# 6_Channel_Pulse_Generator.net
KiCad netlist of a schematic drawn in EAGLE
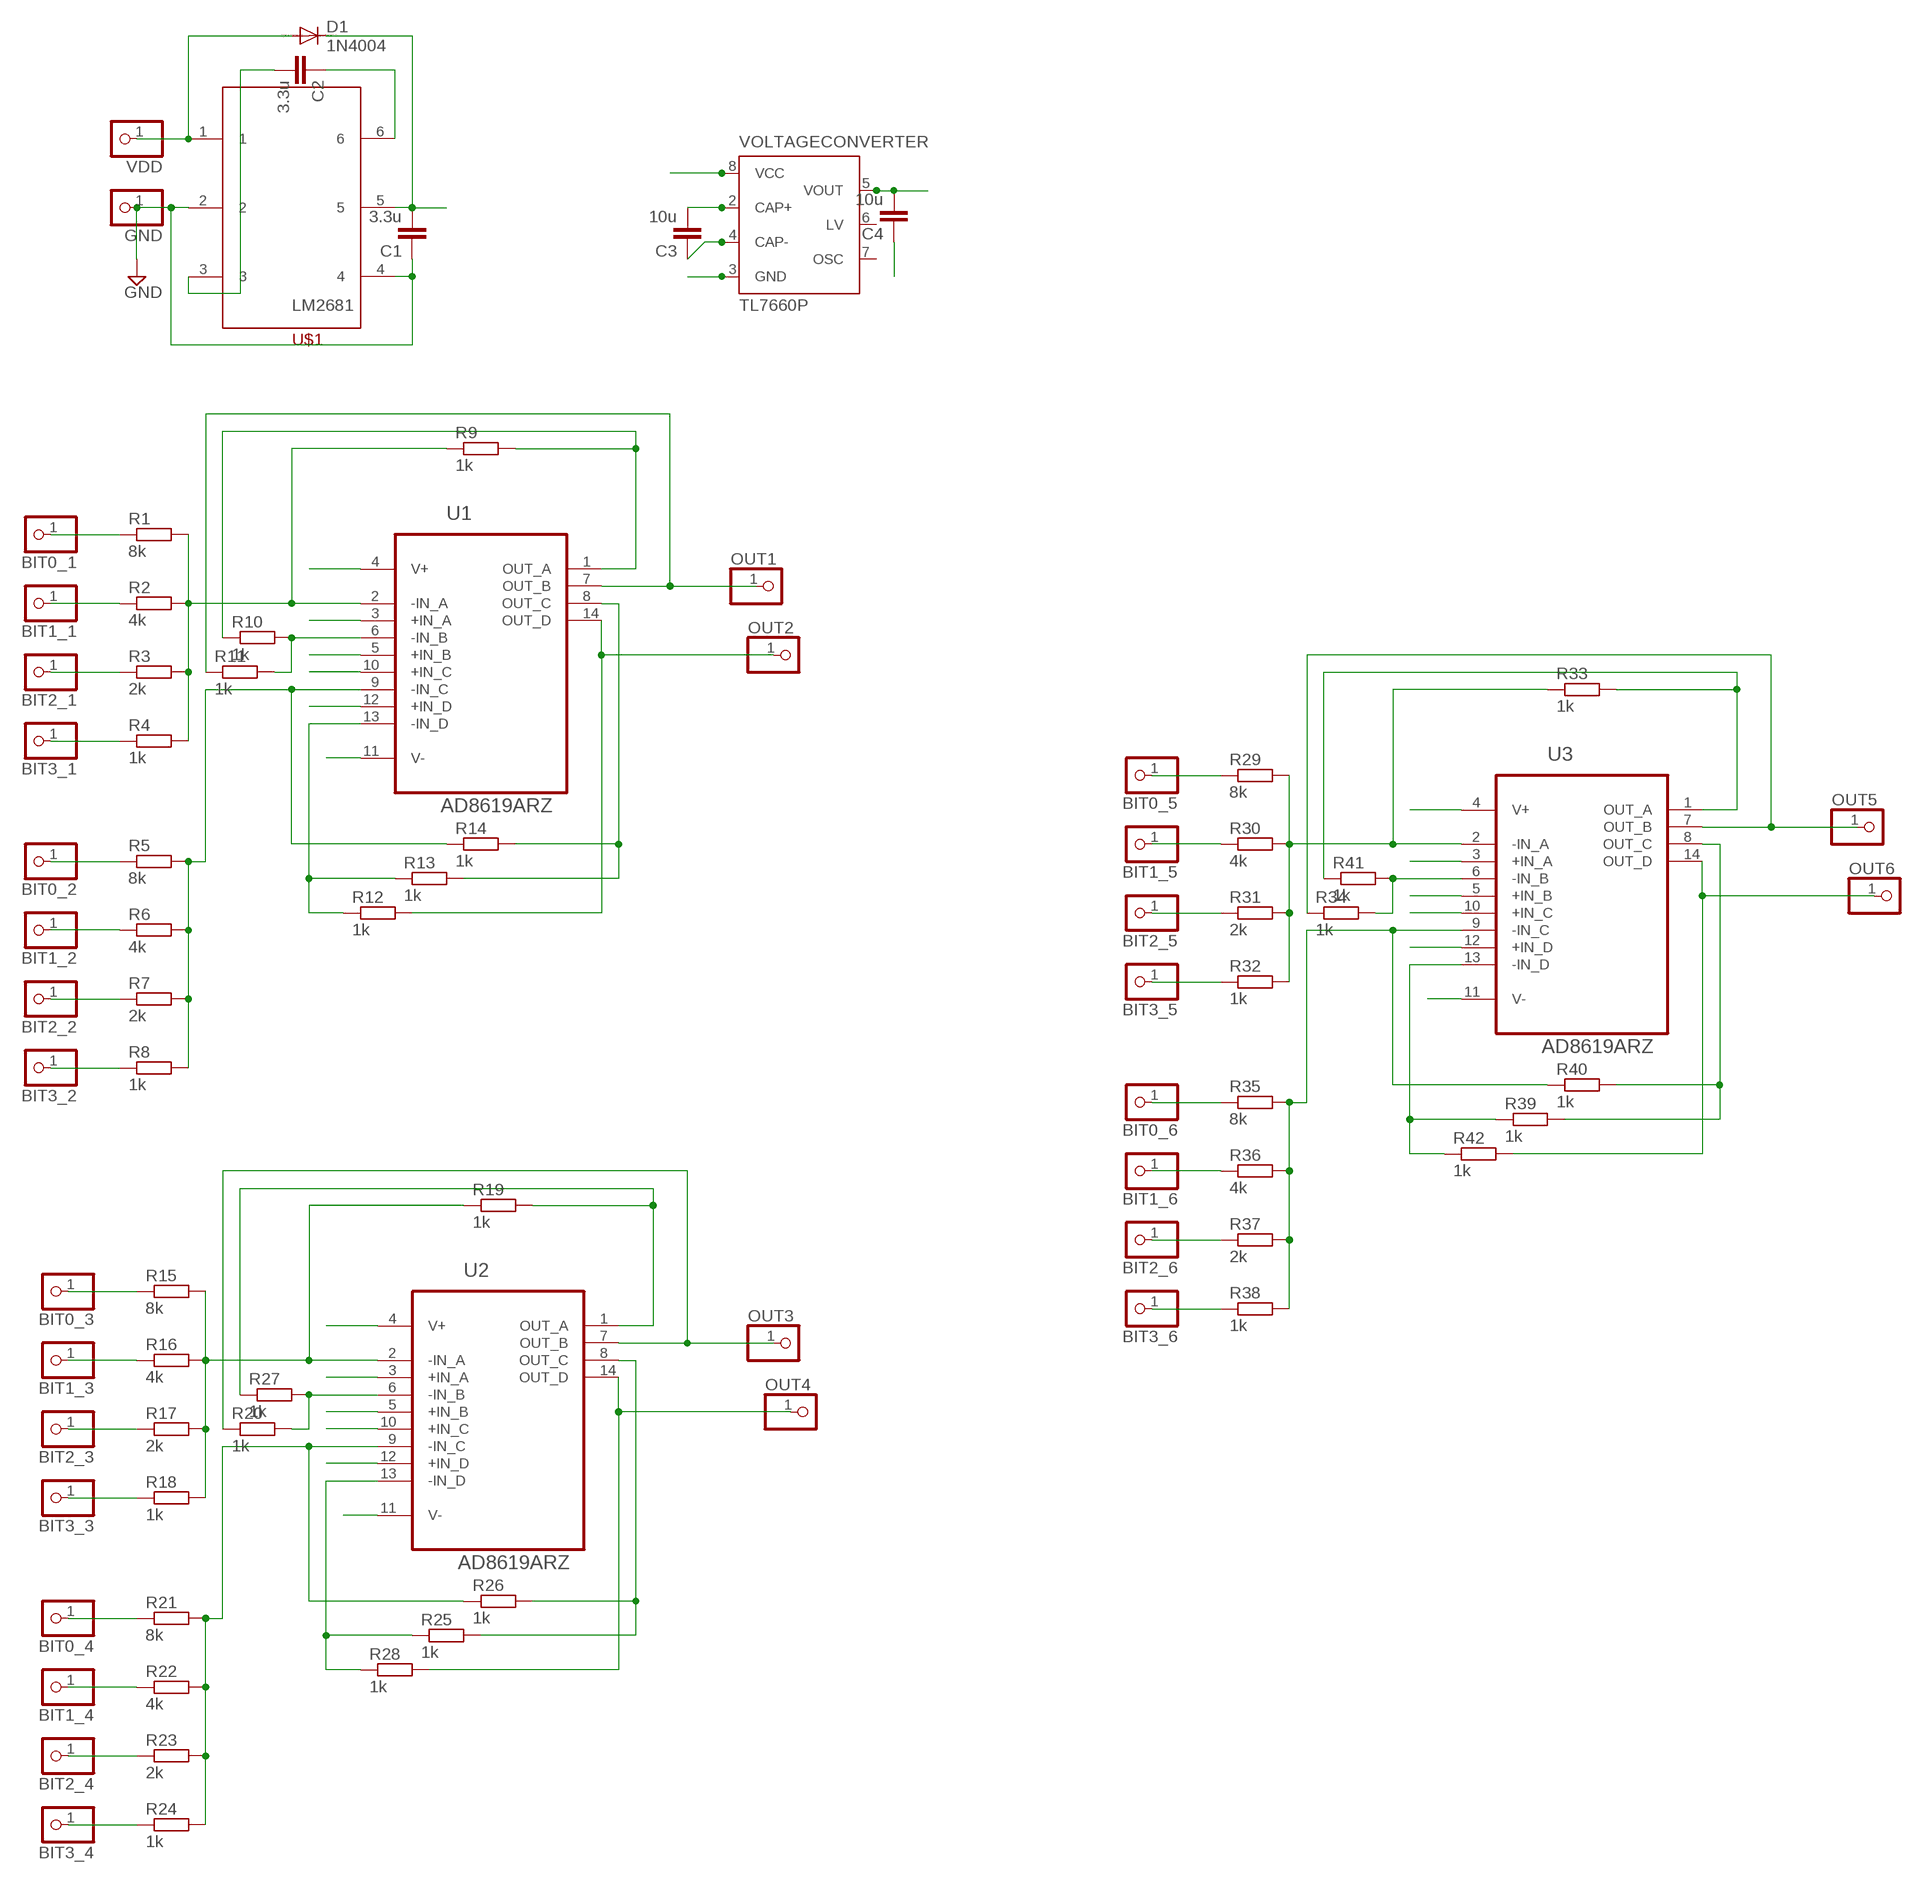
[diagram p0: schematic, sheet 1]

(export (version "E")
  (design (tool "Eeschema 10.0.6"))
  (components
    (comp (ref "BIT0_1")
      (value "PINHD-1X1")
      (footprint "eagle-import:1X01")
      (libsource (lib "eagle-import") (part "PINHD-1X1"))
    )
    (comp (ref "BIT0_2")
      (value "PINHD-1X1")
      (footprint "eagle-import:1X01")
      (libsource (lib "eagle-import") (part "PINHD-1X1"))
    )
    (comp (ref "BIT0_3")
      (value "PINHD-1X1")
      (footprint "eagle-import:1X01")
      (libsource (lib "eagle-import") (part "PINHD-1X1"))
    )
    (comp (ref "BIT0_4")
      (value "PINHD-1X1")
      (footprint "eagle-import:1X01")
      (libsource (lib "eagle-import") (part "PINHD-1X1"))
    )
    (comp (ref "BIT0_5")
      (value "PINHD-1X1")
      (footprint "eagle-import:1X01")
      (libsource (lib "eagle-import") (part "PINHD-1X1"))
    )
    (comp (ref "BIT0_6")
      (value "PINHD-1X1")
      (footprint "eagle-import:1X01")
      (libsource (lib "eagle-import") (part "PINHD-1X1"))
    )
    (comp (ref "BIT1_1")
      (value "PINHD-1X1")
      (footprint "eagle-import:1X01")
      (libsource (lib "eagle-import") (part "PINHD-1X1"))
    )
    (comp (ref "BIT1_2")
      (value "PINHD-1X1")
      (footprint "eagle-import:1X01")
      (libsource (lib "eagle-import") (part "PINHD-1X1"))
    )
    (comp (ref "BIT1_3")
      (value "PINHD-1X1")
      (footprint "eagle-import:1X01")
      (libsource (lib "eagle-import") (part "PINHD-1X1"))
    )
    (comp (ref "BIT1_4")
      (value "PINHD-1X1")
      (footprint "eagle-import:1X01")
      (libsource (lib "eagle-import") (part "PINHD-1X1"))
    )
    (comp (ref "BIT1_5")
      (value "PINHD-1X1")
      (footprint "eagle-import:1X01")
      (libsource (lib "eagle-import") (part "PINHD-1X1"))
    )
    (comp (ref "BIT1_6")
      (value "PINHD-1X1")
      (footprint "eagle-import:1X01")
      (libsource (lib "eagle-import") (part "PINHD-1X1"))
    )
    (comp (ref "BIT2_1")
      (value "PINHD-1X1")
      (footprint "eagle-import:1X01")
      (libsource (lib "eagle-import") (part "PINHD-1X1"))
    )
    (comp (ref "BIT2_2")
      (value "PINHD-1X1")
      (footprint "eagle-import:1X01")
      (libsource (lib "eagle-import") (part "PINHD-1X1"))
    )
    (comp (ref "BIT2_3")
      (value "PINHD-1X1")
      (footprint "eagle-import:1X01")
      (libsource (lib "eagle-import") (part "PINHD-1X1"))
    )
    (comp (ref "BIT2_4")
      (value "PINHD-1X1")
      (footprint "eagle-import:1X01")
      (libsource (lib "eagle-import") (part "PINHD-1X1"))
    )
    (comp (ref "BIT2_5")
      (value "PINHD-1X1")
      (footprint "eagle-import:1X01")
      (libsource (lib "eagle-import") (part "PINHD-1X1"))
    )
    (comp (ref "BIT2_6")
      (value "PINHD-1X1")
      (footprint "eagle-import:1X01")
      (libsource (lib "eagle-import") (part "PINHD-1X1"))
    )
    (comp (ref "BIT3_1")
      (value "PINHD-1X1")
      (footprint "eagle-import:1X01")
      (libsource (lib "eagle-import") (part "PINHD-1X1"))
    )
    (comp (ref "BIT3_2")
      (value "PINHD-1X1")
      (footprint "eagle-import:1X01")
      (libsource (lib "eagle-import") (part "PINHD-1X1"))
    )
    (comp (ref "BIT3_3")
      (value "PINHD-1X1")
      (footprint "eagle-import:1X01")
      (libsource (lib "eagle-import") (part "PINHD-1X1"))
    )
    (comp (ref "BIT3_4")
      (value "PINHD-1X1")
      (footprint "eagle-import:1X01")
      (libsource (lib "eagle-import") (part "PINHD-1X1"))
    )
    (comp (ref "BIT3_5")
      (value "PINHD-1X1")
      (footprint "eagle-import:1X01")
      (libsource (lib "eagle-import") (part "PINHD-1X1"))
    )
    (comp (ref "BIT3_6")
      (value "PINHD-1X1")
      (footprint "eagle-import:1X01")
      (libsource (lib "eagle-import") (part "PINHD-1X1"))
    )
    (comp (ref "C1")
      (value "3.3u")
      (footprint "eagle-import:C1206")
      (libsource (lib "eagle-import") (part "C-EUC1206"))
    )
    (comp (ref "C2")
      (value "3.3u")
      (footprint "eagle-import:C1206")
      (libsource (lib "eagle-import") (part "C-EUC1206"))
    )
    (comp (ref "C3")
      (value "10u")
      (footprint "eagle-import:C1206")
      (libsource (lib "eagle-import") (part "C-EUC1206"))
    )
    (comp (ref "C4")
      (value "10u")
      (footprint "eagle-import:C1206")
      (libsource (lib "eagle-import") (part "C-EUC1206"))
    )
    (comp (ref "D1")
      (value "1N4004")
      (footprint "eagle-import:DO41-10")
      (libsource (lib "eagle-import") (part "1N4004"))
    )
    (comp (ref "GND")
      (value "PINHD-1X1")
      (footprint "eagle-import:1X01")
      (libsource (lib "eagle-import") (part "PINHD-1X1"))
    )
    (comp (ref "OUT1")
      (value "PINHD-1X1")
      (footprint "eagle-import:1X01")
      (libsource (lib "eagle-import") (part "PINHD-1X1"))
    )
    (comp (ref "OUT2")
      (value "PINHD-1X1")
      (footprint "eagle-import:1X01")
      (libsource (lib "eagle-import") (part "PINHD-1X1"))
    )
    (comp (ref "OUT3")
      (value "PINHD-1X1")
      (footprint "eagle-import:1X01")
      (libsource (lib "eagle-import") (part "PINHD-1X1"))
    )
    (comp (ref "OUT4")
      (value "PINHD-1X1")
      (footprint "eagle-import:1X01")
      (libsource (lib "eagle-import") (part "PINHD-1X1"))
    )
    (comp (ref "OUT5")
      (value "PINHD-1X1")
      (footprint "eagle-import:1X01")
      (libsource (lib "eagle-import") (part "PINHD-1X1"))
    )
    (comp (ref "OUT6")
      (value "PINHD-1X1")
      (footprint "eagle-import:1X01")
      (libsource (lib "eagle-import") (part "PINHD-1X1"))
    )
    (comp (ref "R1")
      (value "8k")
      (footprint "eagle-import:M1206")
      (libsource (lib "eagle-import") (part "R-EU_M1206"))
    )
    (comp (ref "R2")
      (value "4k")
      (footprint "eagle-import:M1206")
      (libsource (lib "eagle-import") (part "R-EU_M1206"))
    )
    (comp (ref "R3")
      (value "2k")
      (footprint "eagle-import:M1206")
      (libsource (lib "eagle-import") (part "R-EU_M1206"))
    )
    (comp (ref "R4")
      (value "1k")
      (footprint "eagle-import:M1206")
      (libsource (lib "eagle-import") (part "R-EU_M1206"))
    )
    (comp (ref "R5")
      (value "8k")
      (footprint "eagle-import:M1206")
      (libsource (lib "eagle-import") (part "R-EU_M1206"))
    )
    (comp (ref "R6")
      (value "4k")
      (footprint "eagle-import:M1206")
      (libsource (lib "eagle-import") (part "R-EU_M1206"))
    )
    (comp (ref "R7")
      (value "2k")
      (footprint "eagle-import:M1206")
      (libsource (lib "eagle-import") (part "R-EU_M1206"))
    )
    (comp (ref "R8")
      (value "1k")
      (footprint "eagle-import:M1206")
      (libsource (lib "eagle-import") (part "R-EU_M1206"))
    )
    (comp (ref "R9")
      (value "1k")
      (footprint "eagle-import:M1206")
      (libsource (lib "eagle-import") (part "R-EU_M1206"))
    )
    (comp (ref "R10")
      (value "1k")
      (footprint "eagle-import:M1206")
      (libsource (lib "eagle-import") (part "R-EU_M1206"))
    )
    (comp (ref "R11")
      (value "1k")
      (footprint "eagle-import:M1206")
      (libsource (lib "eagle-import") (part "R-EU_M1206"))
    )
    (comp (ref "R12")
      (value "1k")
      (footprint "eagle-import:M1206")
      (libsource (lib "eagle-import") (part "R-EU_M1206"))
    )
    (comp (ref "R13")
      (value "1k")
      (footprint "eagle-import:M1206")
      (libsource (lib "eagle-import") (part "R-EU_M1206"))
    )
    (comp (ref "R14")
      (value "1k")
      (footprint "eagle-import:M1206")
      (libsource (lib "eagle-import") (part "R-EU_M1206"))
    )
    (comp (ref "R15")
      (value "8k")
      (footprint "eagle-import:M1206")
      (libsource (lib "eagle-import") (part "R-EU_M1206"))
    )
    (comp (ref "R16")
      (value "4k")
      (footprint "eagle-import:M1206")
      (libsource (lib "eagle-import") (part "R-EU_M1206"))
    )
    (comp (ref "R17")
      (value "2k")
      (footprint "eagle-import:M1206")
      (libsource (lib "eagle-import") (part "R-EU_M1206"))
    )
    (comp (ref "R18")
      (value "1k")
      (footprint "eagle-import:M1206")
      (libsource (lib "eagle-import") (part "R-EU_M1206"))
    )
    (comp (ref "R19")
      (value "1k")
      (footprint "eagle-import:M1206")
      (libsource (lib "eagle-import") (part "R-EU_M1206"))
    )
    (comp (ref "R20")
      (value "1k")
      (footprint "eagle-import:M1206")
      (libsource (lib "eagle-import") (part "R-EU_M1206"))
    )
    (comp (ref "R21")
      (value "8k")
      (footprint "eagle-import:M1206")
      (libsource (lib "eagle-import") (part "R-EU_M1206"))
    )
    (comp (ref "R22")
      (value "4k")
      (footprint "eagle-import:M1206")
      (libsource (lib "eagle-import") (part "R-EU_M1206"))
    )
    (comp (ref "R23")
      (value "2k")
      (footprint "eagle-import:M1206")
      (libsource (lib "eagle-import") (part "R-EU_M1206"))
    )
    (comp (ref "R24")
      (value "1k")
      (footprint "eagle-import:M1206")
      (libsource (lib "eagle-import") (part "R-EU_M1206"))
    )
    (comp (ref "R25")
      (value "1k")
      (footprint "eagle-import:M1206")
      (libsource (lib "eagle-import") (part "R-EU_M1206"))
    )
    (comp (ref "R26")
      (value "1k")
      (footprint "eagle-import:M1206")
      (libsource (lib "eagle-import") (part "R-EU_M1206"))
    )
    (comp (ref "R27")
      (value "1k")
      (footprint "eagle-import:M1206")
      (libsource (lib "eagle-import") (part "R-EU_M1206"))
    )
    (comp (ref "R28")
      (value "1k")
      (footprint "eagle-import:M1206")
      (libsource (lib "eagle-import") (part "R-EU_M1206"))
    )
    (comp (ref "R29")
      (value "8k")
      (footprint "eagle-import:M1206")
      (libsource (lib "eagle-import") (part "R-EU_M1206"))
    )
    (comp (ref "R30")
      (value "4k")
      (footprint "eagle-import:M1206")
      (libsource (lib "eagle-import") (part "R-EU_M1206"))
    )
    (comp (ref "R31")
      (value "2k")
      (footprint "eagle-import:M1206")
      (libsource (lib "eagle-import") (part "R-EU_M1206"))
    )
    (comp (ref "R32")
      (value "1k")
      (footprint "eagle-import:M1206")
      (libsource (lib "eagle-import") (part "R-EU_M1206"))
    )
    (comp (ref "R33")
      (value "1k")
      (footprint "eagle-import:M1206")
      (libsource (lib "eagle-import") (part "R-EU_M1206"))
    )
    (comp (ref "R34")
      (value "1k")
      (footprint "eagle-import:M1206")
      (libsource (lib "eagle-import") (part "R-EU_M1206"))
    )
    (comp (ref "R35")
      (value "8k")
      (footprint "eagle-import:M1206")
      (libsource (lib "eagle-import") (part "R-EU_M1206"))
    )
    (comp (ref "R36")
      (value "4k")
      (footprint "eagle-import:M1206")
      (libsource (lib "eagle-import") (part "R-EU_M1206"))
    )
    (comp (ref "R37")
      (value "2k")
      (footprint "eagle-import:M1206")
      (libsource (lib "eagle-import") (part "R-EU_M1206"))
    )
    (comp (ref "R38")
      (value "1k")
      (footprint "eagle-import:M1206")
      (libsource (lib "eagle-import") (part "R-EU_M1206"))
    )
    (comp (ref "R39")
      (value "1k")
      (footprint "eagle-import:M1206")
      (libsource (lib "eagle-import") (part "R-EU_M1206"))
    )
    (comp (ref "R40")
      (value "1k")
      (footprint "eagle-import:M1206")
      (libsource (lib "eagle-import") (part "R-EU_M1206"))
    )
    (comp (ref "R41")
      (value "1k")
      (footprint "eagle-import:M1206")
      (libsource (lib "eagle-import") (part "R-EU_M1206"))
    )
    (comp (ref "R42")
      (value "1k")
      (footprint "eagle-import:M1206")
      (libsource (lib "eagle-import") (part "R-EU_M1206"))
    )
    (comp (ref "U$1")
      (value "LM2681")
      (footprint "eagle-import:LM2681")
      (libsource (lib "eagle-import") (part "LM2681"))
    )
    (comp (ref "U1")
      (value "AD8619ARZ")
      (footprint "eagle-import:SOIC127P600X175-14N")
      (fields (field (name "MF") "Analog Devices"))
      (libsource (lib "eagle-import") (part "AD8619ARZ"))
    )
    (comp (ref "U2")
      (value "AD8619ARZ")
      (footprint "eagle-import:SOIC127P600X175-14N")
      (fields (field (name "MF") "Analog Devices"))
      (libsource (lib "eagle-import") (part "AD8619ARZ"))
    )
    (comp (ref "U3")
      (value "AD8619ARZ")
      (footprint "eagle-import:SOIC127P600X175-14N")
      (fields (field (name "MF") "Analog Devices"))
      (libsource (lib "eagle-import") (part "AD8619ARZ"))
    )
    (comp (ref "VDD")
      (value "PINHD-1X1")
      (footprint "eagle-import:1X01")
      (libsource (lib "eagle-import") (part "PINHD-1X1"))
    )
    (comp (ref "VOLTAGECONVERTER")
      (value "TL7660P")
      (footprint "eagle-import:DIL08")
      (fields (field (name "MPN") "TL7660CP"))
      (libsource (lib "eagle-import") (part "TL7660P"))
    )
  )
  (nets
    (net (code "1") (name "/VDD") (class "Default")
      (node (ref "C1") (pin "2") (pinfunction "2_2") (pintype "passive"))
      (node (ref "D1") (pin "C") (pinfunction "C_C") (pintype "passive"))
      (node (ref "U$1") (pin "5") (pinfunction "5_5") (pintype "bidirectional"))
      (node (ref "U1") (pin "4") (pinfunction "V+_4") (pintype "power_in"))
      (node (ref "U2") (pin "4") (pinfunction "V+_4") (pintype "power_in"))
      (node (ref "U3") (pin "4") (pinfunction "V+_4") (pintype "power_in"))
      (node (ref "VOLTAGECONVERTER") (pin "8") (pinfunction "VCC_8") (pintype "power_in"))
    )
    (net (code "2") (name "/VDD-") (class "Default")
      (node (ref "C4") (pin "2") (pinfunction "2_2") (pintype "passive"))
      (node (ref "U1") (pin "11") (pinfunction "V-_11") (pintype "power_in"))
      (node (ref "U2") (pin "11") (pinfunction "V-_11") (pintype "power_in"))
      (node (ref "U3") (pin "11") (pinfunction "V-_11") (pintype "power_in"))
      (node (ref "VOLTAGECONVERTER") (pin "5") (pinfunction "VOUT_5") (pintype "passive"))
    )
    (net (code "3") (name "GND") (class "Default")
      (node (ref "C1") (pin "1") (pinfunction "1_1") (pintype "passive"))
      (node (ref "C4") (pin "1") (pinfunction "1_1") (pintype "passive"))
      (node (ref "GND") (pin "1") (pinfunction "1_1") (pintype "passive"))
      (node (ref "U$1") (pin "2") (pinfunction "2_2") (pintype "bidirectional"))
      (node (ref "U$1") (pin "4") (pinfunction "4_4") (pintype "bidirectional"))
      (node (ref "U1") (pin "10") (pinfunction "+IN_C_10") (pintype "input"))
      (node (ref "U1") (pin "12") (pinfunction "+IN_D_12") (pintype "input"))
      (node (ref "U1") (pin "3") (pinfunction "+IN_A_3") (pintype "input"))
      (node (ref "U1") (pin "5") (pinfunction "+IN_B_5") (pintype "input"))
      (node (ref "U2") (pin "10") (pinfunction "+IN_C_10") (pintype "input"))
      (node (ref "U2") (pin "12") (pinfunction "+IN_D_12") (pintype "input"))
      (node (ref "U2") (pin "3") (pinfunction "+IN_A_3") (pintype "input"))
      (node (ref "U2") (pin "5") (pinfunction "+IN_B_5") (pintype "input"))
      (node (ref "U3") (pin "10") (pinfunction "+IN_C_10") (pintype "input"))
      (node (ref "U3") (pin "12") (pinfunction "+IN_D_12") (pintype "input"))
      (node (ref "U3") (pin "3") (pinfunction "+IN_A_3") (pintype "input"))
      (node (ref "U3") (pin "5") (pinfunction "+IN_B_5") (pintype "input"))
      (node (ref "VOLTAGECONVERTER") (pin "3") (pinfunction "GND_3") (pintype "power_in"))
    )
    (net (code "4") (name "Net-(BIT0_1-Pad1)") (class "Default")
      (node (ref "BIT0_1") (pin "1") (pinfunction "1_1") (pintype "passive"))
      (node (ref "R1") (pin "1") (pinfunction "1_1") (pintype "passive"))
    )
    (net (code "5") (name "Net-(BIT0_2-Pad1)") (class "Default")
      (node (ref "BIT0_2") (pin "1") (pinfunction "1_1") (pintype "passive"))
      (node (ref "R5") (pin "1") (pinfunction "1_1") (pintype "passive"))
    )
    (net (code "6") (name "Net-(BIT0_3-Pad1)") (class "Default")
      (node (ref "BIT0_3") (pin "1") (pinfunction "1_1") (pintype "passive"))
      (node (ref "R15") (pin "1") (pinfunction "1_1") (pintype "passive"))
    )
    (net (code "7") (name "Net-(BIT0_4-Pad1)") (class "Default")
      (node (ref "BIT0_4") (pin "1") (pinfunction "1_1") (pintype "passive"))
      (node (ref "R21") (pin "1") (pinfunction "1_1") (pintype "passive"))
    )
    (net (code "8") (name "Net-(BIT0_5-Pad1)") (class "Default")
      (node (ref "BIT0_5") (pin "1") (pinfunction "1_1") (pintype "passive"))
      (node (ref "R29") (pin "1") (pinfunction "1_1") (pintype "passive"))
    )
    (net (code "9") (name "Net-(BIT0_6-Pad1)") (class "Default")
      (node (ref "BIT0_6") (pin "1") (pinfunction "1_1") (pintype "passive"))
      (node (ref "R35") (pin "1") (pinfunction "1_1") (pintype "passive"))
    )
    (net (code "10") (name "Net-(BIT1_1-Pad1)") (class "Default")
      (node (ref "BIT1_1") (pin "1") (pinfunction "1_1") (pintype "passive"))
      (node (ref "R2") (pin "1") (pinfunction "1_1") (pintype "passive"))
    )
    (net (code "11") (name "Net-(BIT1_2-Pad1)") (class "Default")
      (node (ref "BIT1_2") (pin "1") (pinfunction "1_1") (pintype "passive"))
      (node (ref "R6") (pin "1") (pinfunction "1_1") (pintype "passive"))
    )
    (net (code "12") (name "Net-(BIT1_3-Pad1)") (class "Default")
      (node (ref "BIT1_3") (pin "1") (pinfunction "1_1") (pintype "passive"))
      (node (ref "R16") (pin "1") (pinfunction "1_1") (pintype "passive"))
    )
    (net (code "13") (name "Net-(BIT1_4-Pad1)") (class "Default")
      (node (ref "BIT1_4") (pin "1") (pinfunction "1_1") (pintype "passive"))
      (node (ref "R22") (pin "1") (pinfunction "1_1") (pintype "passive"))
    )
    (net (code "14") (name "Net-(BIT1_5-Pad1)") (class "Default")
      (node (ref "BIT1_5") (pin "1") (pinfunction "1_1") (pintype "passive"))
      (node (ref "R30") (pin "1") (pinfunction "1_1") (pintype "passive"))
    )
    (net (code "15") (name "Net-(BIT1_6-Pad1)") (class "Default")
      (node (ref "BIT1_6") (pin "1") (pinfunction "1_1") (pintype "passive"))
      (node (ref "R36") (pin "1") (pinfunction "1_1") (pintype "passive"))
    )
    (net (code "16") (name "Net-(BIT2_1-Pad1)") (class "Default")
      (node (ref "BIT2_1") (pin "1") (pinfunction "1_1") (pintype "passive"))
      (node (ref "R3") (pin "1") (pinfunction "1_1") (pintype "passive"))
    )
    (net (code "17") (name "Net-(BIT2_2-Pad1)") (class "Default")
      (node (ref "BIT2_2") (pin "1") (pinfunction "1_1") (pintype "passive"))
      (node (ref "R7") (pin "1") (pinfunction "1_1") (pintype "passive"))
    )
    (net (code "18") (name "Net-(BIT2_3-Pad1)") (class "Default")
      (node (ref "BIT2_3") (pin "1") (pinfunction "1_1") (pintype "passive"))
      (node (ref "R17") (pin "1") (pinfunction "1_1") (pintype "passive"))
    )
    (net (code "19") (name "Net-(BIT2_4-Pad1)") (class "Default")
      (node (ref "BIT2_4") (pin "1") (pinfunction "1_1") (pintype "passive"))
      (node (ref "R23") (pin "1") (pinfunction "1_1") (pintype "passive"))
    )
    (net (code "20") (name "Net-(BIT2_5-Pad1)") (class "Default")
      (node (ref "BIT2_5") (pin "1") (pinfunction "1_1") (pintype "passive"))
      (node (ref "R31") (pin "1") (pinfunction "1_1") (pintype "passive"))
    )
    (net (code "21") (name "Net-(BIT2_6-Pad1)") (class "Default")
      (node (ref "BIT2_6") (pin "1") (pinfunction "1_1") (pintype "passive"))
      (node (ref "R37") (pin "1") (pinfunction "1_1") (pintype "passive"))
    )
    (net (code "22") (name "Net-(BIT3_1-Pad1)") (class "Default")
      (node (ref "BIT3_1") (pin "1") (pinfunction "1_1") (pintype "passive"))
      (node (ref "R4") (pin "1") (pinfunction "1_1") (pintype "passive"))
    )
    (net (code "23") (name "Net-(BIT3_2-Pad1)") (class "Default")
      (node (ref "BIT3_2") (pin "1") (pinfunction "1_1") (pintype "passive"))
      (node (ref "R8") (pin "1") (pinfunction "1_1") (pintype "passive"))
    )
    (net (code "24") (name "Net-(BIT3_3-Pad1)") (class "Default")
      (node (ref "BIT3_3") (pin "1") (pinfunction "1_1") (pintype "passive"))
      (node (ref "R18") (pin "1") (pinfunction "1_1") (pintype "passive"))
    )
    (net (code "25") (name "Net-(BIT3_4-Pad1)") (class "Default")
      (node (ref "BIT3_4") (pin "1") (pinfunction "1_1") (pintype "passive"))
      (node (ref "R24") (pin "1") (pinfunction "1_1") (pintype "passive"))
    )
    (net (code "26") (name "Net-(BIT3_5-Pad1)") (class "Default")
      (node (ref "BIT3_5") (pin "1") (pinfunction "1_1") (pintype "passive"))
      (node (ref "R32") (pin "1") (pinfunction "1_1") (pintype "passive"))
    )
    (net (code "27") (name "Net-(BIT3_6-Pad1)") (class "Default")
      (node (ref "BIT3_6") (pin "1") (pinfunction "1_1") (pintype "passive"))
      (node (ref "R38") (pin "1") (pinfunction "1_1") (pintype "passive"))
    )
    (net (code "28") (name "Net-(C2-Pad1)") (class "Default")
      (node (ref "C2") (pin "1") (pinfunction "1_1") (pintype "passive"))
      (node (ref "U$1") (pin "6") (pinfunction "6_6") (pintype "bidirectional"))
    )
    (net (code "29") (name "Net-(C2-Pad2)") (class "Default")
      (node (ref "C2") (pin "2") (pinfunction "2_2") (pintype "passive"))
      (node (ref "U$1") (pin "3") (pinfunction "3_3") (pintype "bidirectional"))
    )
    (net (code "30") (name "Net-(D1-PadA)") (class "Default")
      (node (ref "D1") (pin "A") (pinfunction "A_A") (pintype "passive"))
      (node (ref "U$1") (pin "1") (pinfunction "1_1") (pintype "bidirectional"))
      (node (ref "VDD") (pin "1") (pinfunction "1_1") (pintype "passive"))
    )
    (net (code "31") (name "Net-(U1--IN_A)") (class "Default")
      (node (ref "R1") (pin "2") (pinfunction "2_2") (pintype "passive"))
      (node (ref "R2") (pin "2") (pinfunction "2_2") (pintype "passive"))
      (node (ref "R3") (pin "2") (pinfunction "2_2") (pintype "passive"))
      (node (ref "R4") (pin "2") (pinfunction "2_2") (pintype "passive"))
      (node (ref "R9") (pin "1") (pinfunction "1_1") (pintype "passive"))
      (node (ref "U1") (pin "2") (pinfunction "-IN_A_2") (pintype "input"))
    )
    (net (code "32") (name "Net-(U1--IN_B)") (class "Default")
      (node (ref "R10") (pin "2") (pinfunction "2_2") (pintype "passive"))
      (node (ref "R11") (pin "2") (pinfunction "2_2") (pintype "passive"))
      (node (ref "U1") (pin "6") (pinfunction "-IN_B_6") (pintype "input"))
    )
    (net (code "33") (name "Net-(U1--IN_C)") (class "Default")
      (node (ref "R14") (pin "1") (pinfunction "1_1") (pintype "passive"))
      (node (ref "R5") (pin "2") (pinfunction "2_2") (pintype "passive"))
      (node (ref "R6") (pin "2") (pinfunction "2_2") (pintype "passive"))
      (node (ref "R7") (pin "2") (pinfunction "2_2") (pintype "passive"))
      (node (ref "R8") (pin "2") (pinfunction "2_2") (pintype "passive"))
      (node (ref "U1") (pin "9") (pinfunction "-IN_C_9") (pintype "input"))
    )
    (net (code "34") (name "Net-(U1--IN_D)") (class "Default")
      (node (ref "R12") (pin "1") (pinfunction "1_1") (pintype "passive"))
      (node (ref "R13") (pin "1") (pinfunction "1_1") (pintype "passive"))
      (node (ref "U1") (pin "13") (pinfunction "-IN_D_13") (pintype "input"))
    )
    (net (code "35") (name "Net-(U1-OUT_A)") (class "Default")
      (node (ref "R10") (pin "1") (pinfunction "1_1") (pintype "passive"))
      (node (ref "R9") (pin "2") (pinfunction "2_2") (pintype "passive"))
      (node (ref "U1") (pin "1") (pinfunction "OUT_A_1") (pintype "output"))
    )
    (net (code "36") (name "Net-(U1-OUT_B)") (class "Default")
      (node (ref "OUT1") (pin "1") (pinfunction "1_1") (pintype "passive"))
      (node (ref "R11") (pin "1") (pinfunction "1_1") (pintype "passive"))
      (node (ref "U1") (pin "7") (pinfunction "OUT_B_7") (pintype "output"))
    )
    (net (code "37") (name "Net-(U1-OUT_C)") (class "Default")
      (node (ref "R13") (pin "2") (pinfunction "2_2") (pintype "passive"))
      (node (ref "R14") (pin "2") (pinfunction "2_2") (pintype "passive"))
      (node (ref "U1") (pin "8") (pinfunction "OUT_C_8") (pintype "output"))
    )
    (net (code "38") (name "Net-(U1-OUT_D)") (class "Default")
      (node (ref "OUT2") (pin "1") (pinfunction "1_1") (pintype "passive"))
      (node (ref "R12") (pin "2") (pinfunction "2_2") (pintype "passive"))
      (node (ref "U1") (pin "14") (pinfunction "OUT_D_14") (pintype "output"))
    )
    (net (code "39") (name "Net-(U2--IN_A)") (class "Default")
      (node (ref "R15") (pin "2") (pinfunction "2_2") (pintype "passive"))
      (node (ref "R16") (pin "2") (pinfunction "2_2") (pintype "passive"))
      (node (ref "R17") (pin "2") (pinfunction "2_2") (pintype "passive"))
      (node (ref "R18") (pin "2") (pinfunction "2_2") (pintype "passive"))
      (node (ref "R19") (pin "1") (pinfunction "1_1") (pintype "passive"))
      (node (ref "U2") (pin "2") (pinfunction "-IN_A_2") (pintype "input"))
    )
    (net (code "40") (name "Net-(U2--IN_B)") (class "Default")
      (node (ref "R20") (pin "2") (pinfunction "2_2") (pintype "passive"))
      (node (ref "R27") (pin "2") (pinfunction "2_2") (pintype "passive"))
      (node (ref "U2") (pin "6") (pinfunction "-IN_B_6") (pintype "input"))
    )
    (net (code "41") (name "Net-(U2--IN_C)") (class "Default")
      (node (ref "R21") (pin "2") (pinfunction "2_2") (pintype "passive"))
      (node (ref "R22") (pin "2") (pinfunction "2_2") (pintype "passive"))
      (node (ref "R23") (pin "2") (pinfunction "2_2") (pintype "passive"))
      (node (ref "R24") (pin "2") (pinfunction "2_2") (pintype "passive"))
      (node (ref "R26") (pin "1") (pinfunction "1_1") (pintype "passive"))
      (node (ref "U2") (pin "9") (pinfunction "-IN_C_9") (pintype "input"))
    )
    (net (code "42") (name "Net-(U2--IN_D)") (class "Default")
      (node (ref "R25") (pin "1") (pinfunction "1_1") (pintype "passive"))
      (node (ref "R28") (pin "1") (pinfunction "1_1") (pintype "passive"))
      (node (ref "U2") (pin "13") (pinfunction "-IN_D_13") (pintype "input"))
    )
    (net (code "43") (name "Net-(U2-OUT_A)") (class "Default")
      (node (ref "R19") (pin "2") (pinfunction "2_2") (pintype "passive"))
      (node (ref "R27") (pin "1") (pinfunction "1_1") (pintype "passive"))
      (node (ref "U2") (pin "1") (pinfunction "OUT_A_1") (pintype "output"))
    )
    (net (code "44") (name "Net-(U2-OUT_B)") (class "Default")
      (node (ref "OUT3") (pin "1") (pinfunction "1_1") (pintype "passive"))
      (node (ref "R20") (pin "1") (pinfunction "1_1") (pintype "passive"))
      (node (ref "U2") (pin "7") (pinfunction "OUT_B_7") (pintype "output"))
    )
    (net (code "45") (name "Net-(U2-OUT_C)") (class "Default")
      (node (ref "R25") (pin "2") (pinfunction "2_2") (pintype "passive"))
      (node (ref "R26") (pin "2") (pinfunction "2_2") (pintype "passive"))
      (node (ref "U2") (pin "8") (pinfunction "OUT_C_8") (pintype "output"))
    )
    (net (code "46") (name "Net-(U2-OUT_D)") (class "Default")
      (node (ref "OUT4") (pin "1") (pinfunction "1_1") (pintype "passive"))
      (node (ref "R28") (pin "2") (pinfunction "2_2") (pintype "passive"))
      (node (ref "U2") (pin "14") (pinfunction "OUT_D_14") (pintype "output"))
    )
    (net (code "47") (name "Net-(U3--IN_A)") (class "Default")
      (node (ref "R29") (pin "2") (pinfunction "2_2") (pintype "passive"))
      (node (ref "R30") (pin "2") (pinfunction "2_2") (pintype "passive"))
      (node (ref "R31") (pin "2") (pinfunction "2_2") (pintype "passive"))
      (node (ref "R32") (pin "2") (pinfunction "2_2") (pintype "passive"))
      (node (ref "R33") (pin "1") (pinfunction "1_1") (pintype "passive"))
      (node (ref "U3") (pin "2") (pinfunction "-IN_A_2") (pintype "input"))
    )
    (net (code "48") (name "Net-(U3--IN_B)") (class "Default")
      (node (ref "R34") (pin "2") (pinfunction "2_2") (pintype "passive"))
      (node (ref "R41") (pin "2") (pinfunction "2_2") (pintype "passive"))
      (node (ref "U3") (pin "6") (pinfunction "-IN_B_6") (pintype "input"))
    )
    (net (code "49") (name "Net-(U3--IN_C)") (class "Default")
      (node (ref "R35") (pin "2") (pinfunction "2_2") (pintype "passive"))
      (node (ref "R36") (pin "2") (pinfunction "2_2") (pintype "passive"))
      (node (ref "R37") (pin "2") (pinfunction "2_2") (pintype "passive"))
      (node (ref "R38") (pin "2") (pinfunction "2_2") (pintype "passive"))
      (node (ref "R40") (pin "1") (pinfunction "1_1") (pintype "passive"))
      (node (ref "U3") (pin "9") (pinfunction "-IN_C_9") (pintype "input"))
    )
    (net (code "50") (name "Net-(U3--IN_D)") (class "Default")
      (node (ref "R39") (pin "1") (pinfunction "1_1") (pintype "passive"))
      (node (ref "R42") (pin "1") (pinfunction "1_1") (pintype "passive"))
      (node (ref "U3") (pin "13") (pinfunction "-IN_D_13") (pintype "input"))
    )
    (net (code "51") (name "Net-(U3-OUT_A)") (class "Default")
      (node (ref "R33") (pin "2") (pinfunction "2_2") (pintype "passive"))
      (node (ref "R41") (pin "1") (pinfunction "1_1") (pintype "passive"))
      (node (ref "U3") (pin "1") (pinfunction "OUT_A_1") (pintype "output"))
    )
    (net (code "52") (name "Net-(U3-OUT_B)") (class "Default")
      (node (ref "OUT5") (pin "1") (pinfunction "1_1") (pintype "passive"))
      (node (ref "R34") (pin "1") (pinfunction "1_1") (pintype "passive"))
      (node (ref "U3") (pin "7") (pinfunction "OUT_B_7") (pintype "output"))
    )
    (net (code "53") (name "Net-(U3-OUT_C)") (class "Default")
      (node (ref "R39") (pin "2") (pinfunction "2_2") (pintype "passive"))
      (node (ref "R40") (pin "2") (pinfunction "2_2") (pintype "passive"))
      (node (ref "U3") (pin "8") (pinfunction "OUT_C_8") (pintype "output"))
    )
    (net (code "54") (name "Net-(U3-OUT_D)") (class "Default")
      (node (ref "OUT6") (pin "1") (pinfunction "1_1") (pintype "passive"))
      (node (ref "R42") (pin "2") (pinfunction "2_2") (pintype "passive"))
      (node (ref "U3") (pin "14") (pinfunction "OUT_D_14") (pintype "output"))
    )
    (net (code "55") (name "Net-(VOLTAGECONVERTER-CAP+)") (class "Default")
      (node (ref "C3") (pin "2") (pinfunction "2_2") (pintype "passive"))
      (node (ref "VOLTAGECONVERTER") (pin "2") (pinfunction "CAP+_2") (pintype "passive"))
    )
    (net (code "56") (name "Net-(VOLTAGECONVERTER-CAP-)") (class "Default")
      (node (ref "C3") (pin "1") (pinfunction "1_1") (pintype "passive"))
      (node (ref "VOLTAGECONVERTER") (pin "4") (pinfunction "CAP-_4") (pintype "passive"))
    )
    (net (code "57") (name "unconnected-(VOLTAGECONVERTER-LV-Pad6)") (class "Default")
      (node (ref "VOLTAGECONVERTER") (pin "6") (pinfunction "LV_6") (pintype "passive"))
    )
    (net (code "58") (name "unconnected-(VOLTAGECONVERTER-OSC-Pad7)") (class "Default")
      (node (ref "VOLTAGECONVERTER") (pin "7") (pinfunction "OSC_7") (pintype "input"))
    )
  )
)
